# Main-v3_0.net
KiCad netlist of a schematic drawn in EAGLE
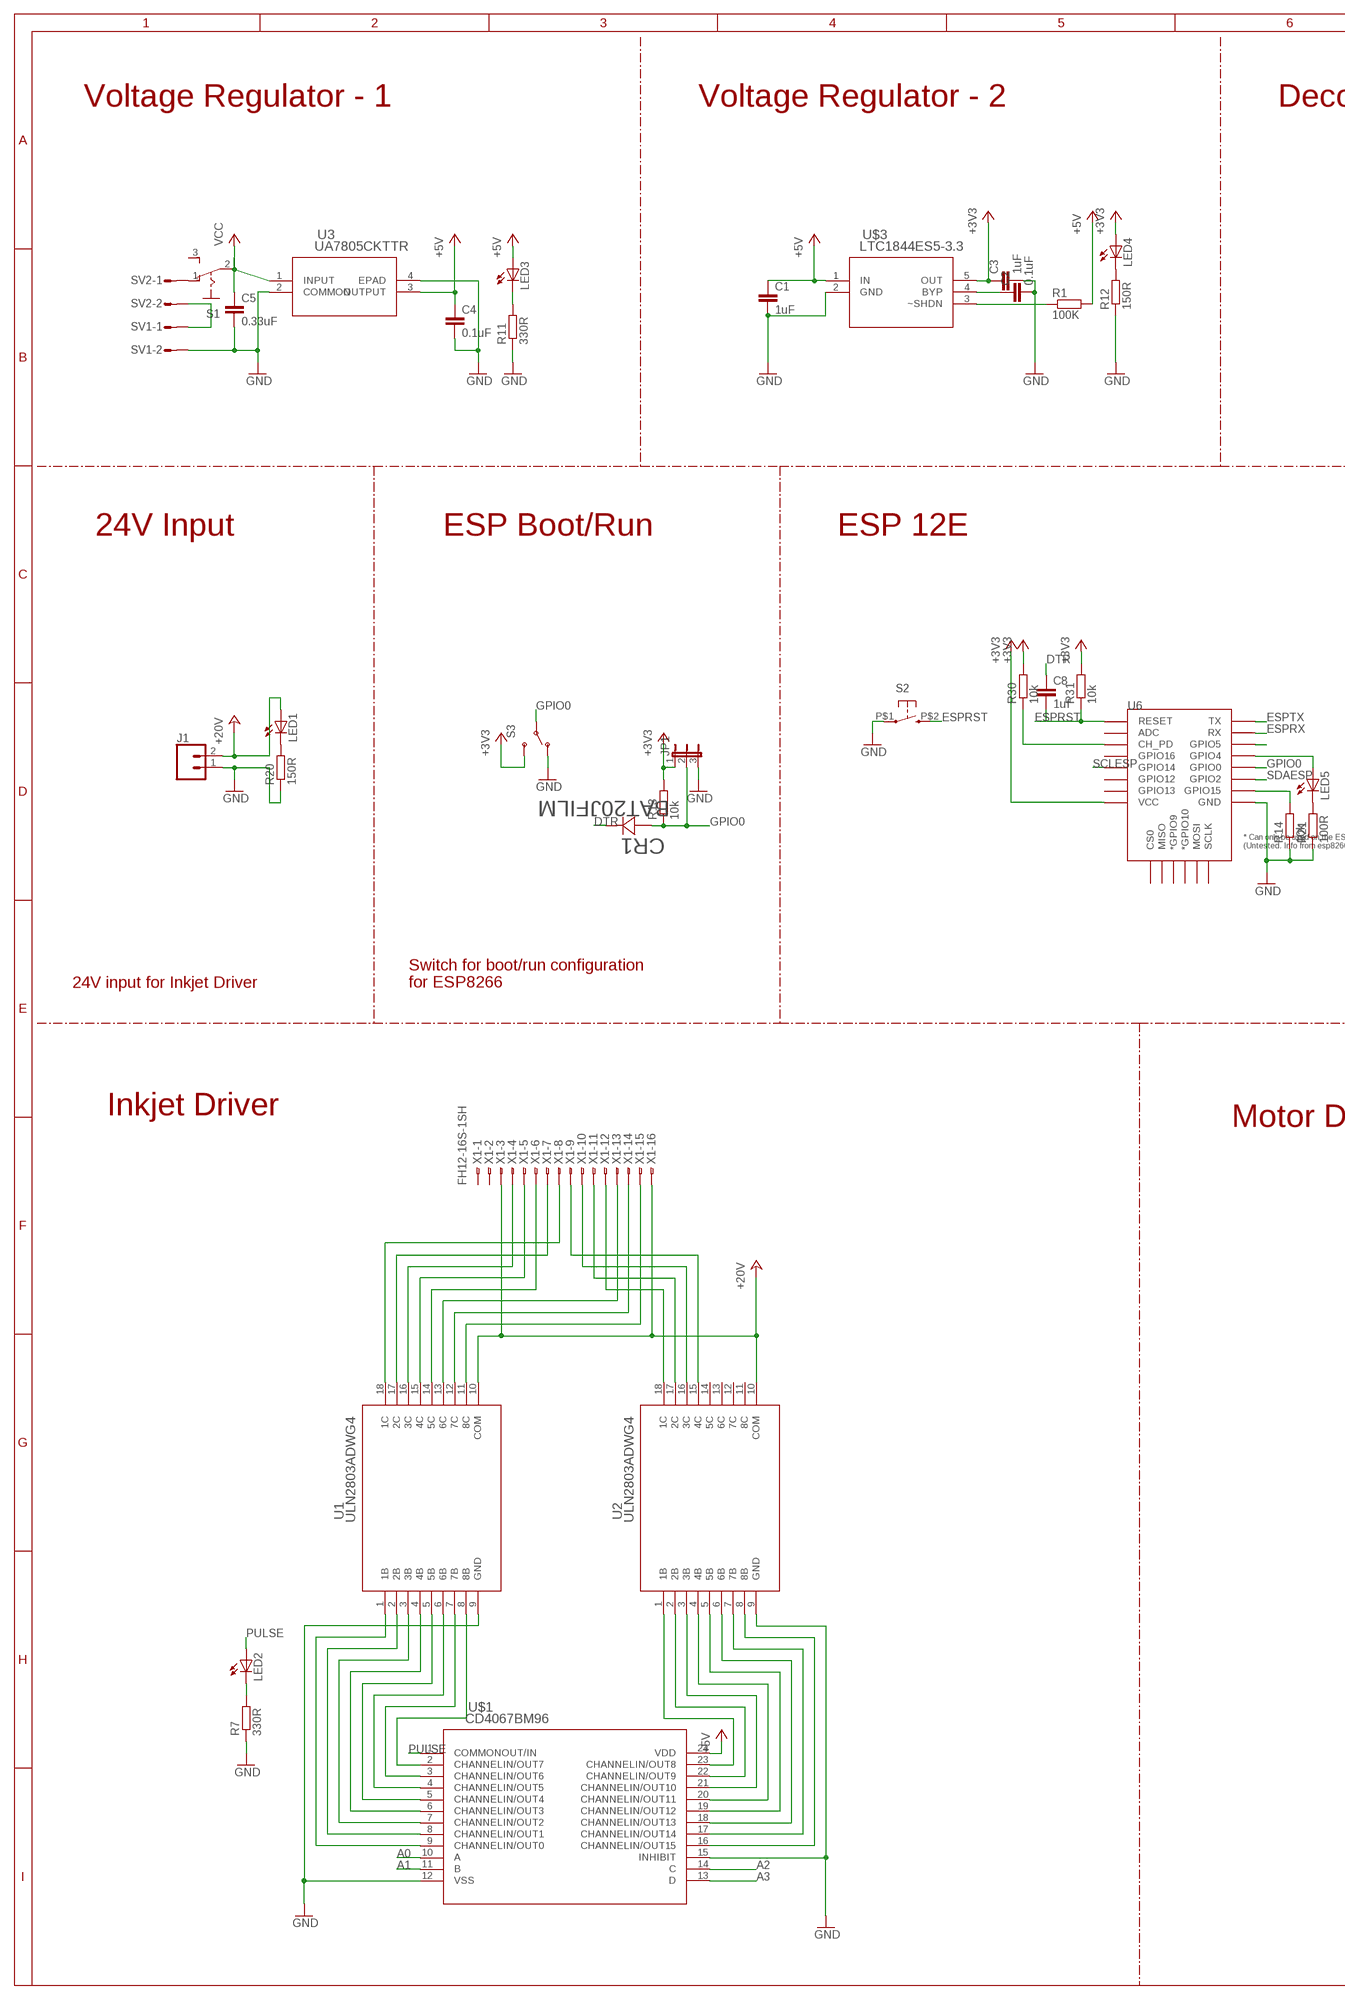
[diagram p0: schematic, sheet 1, part 1 of 2]
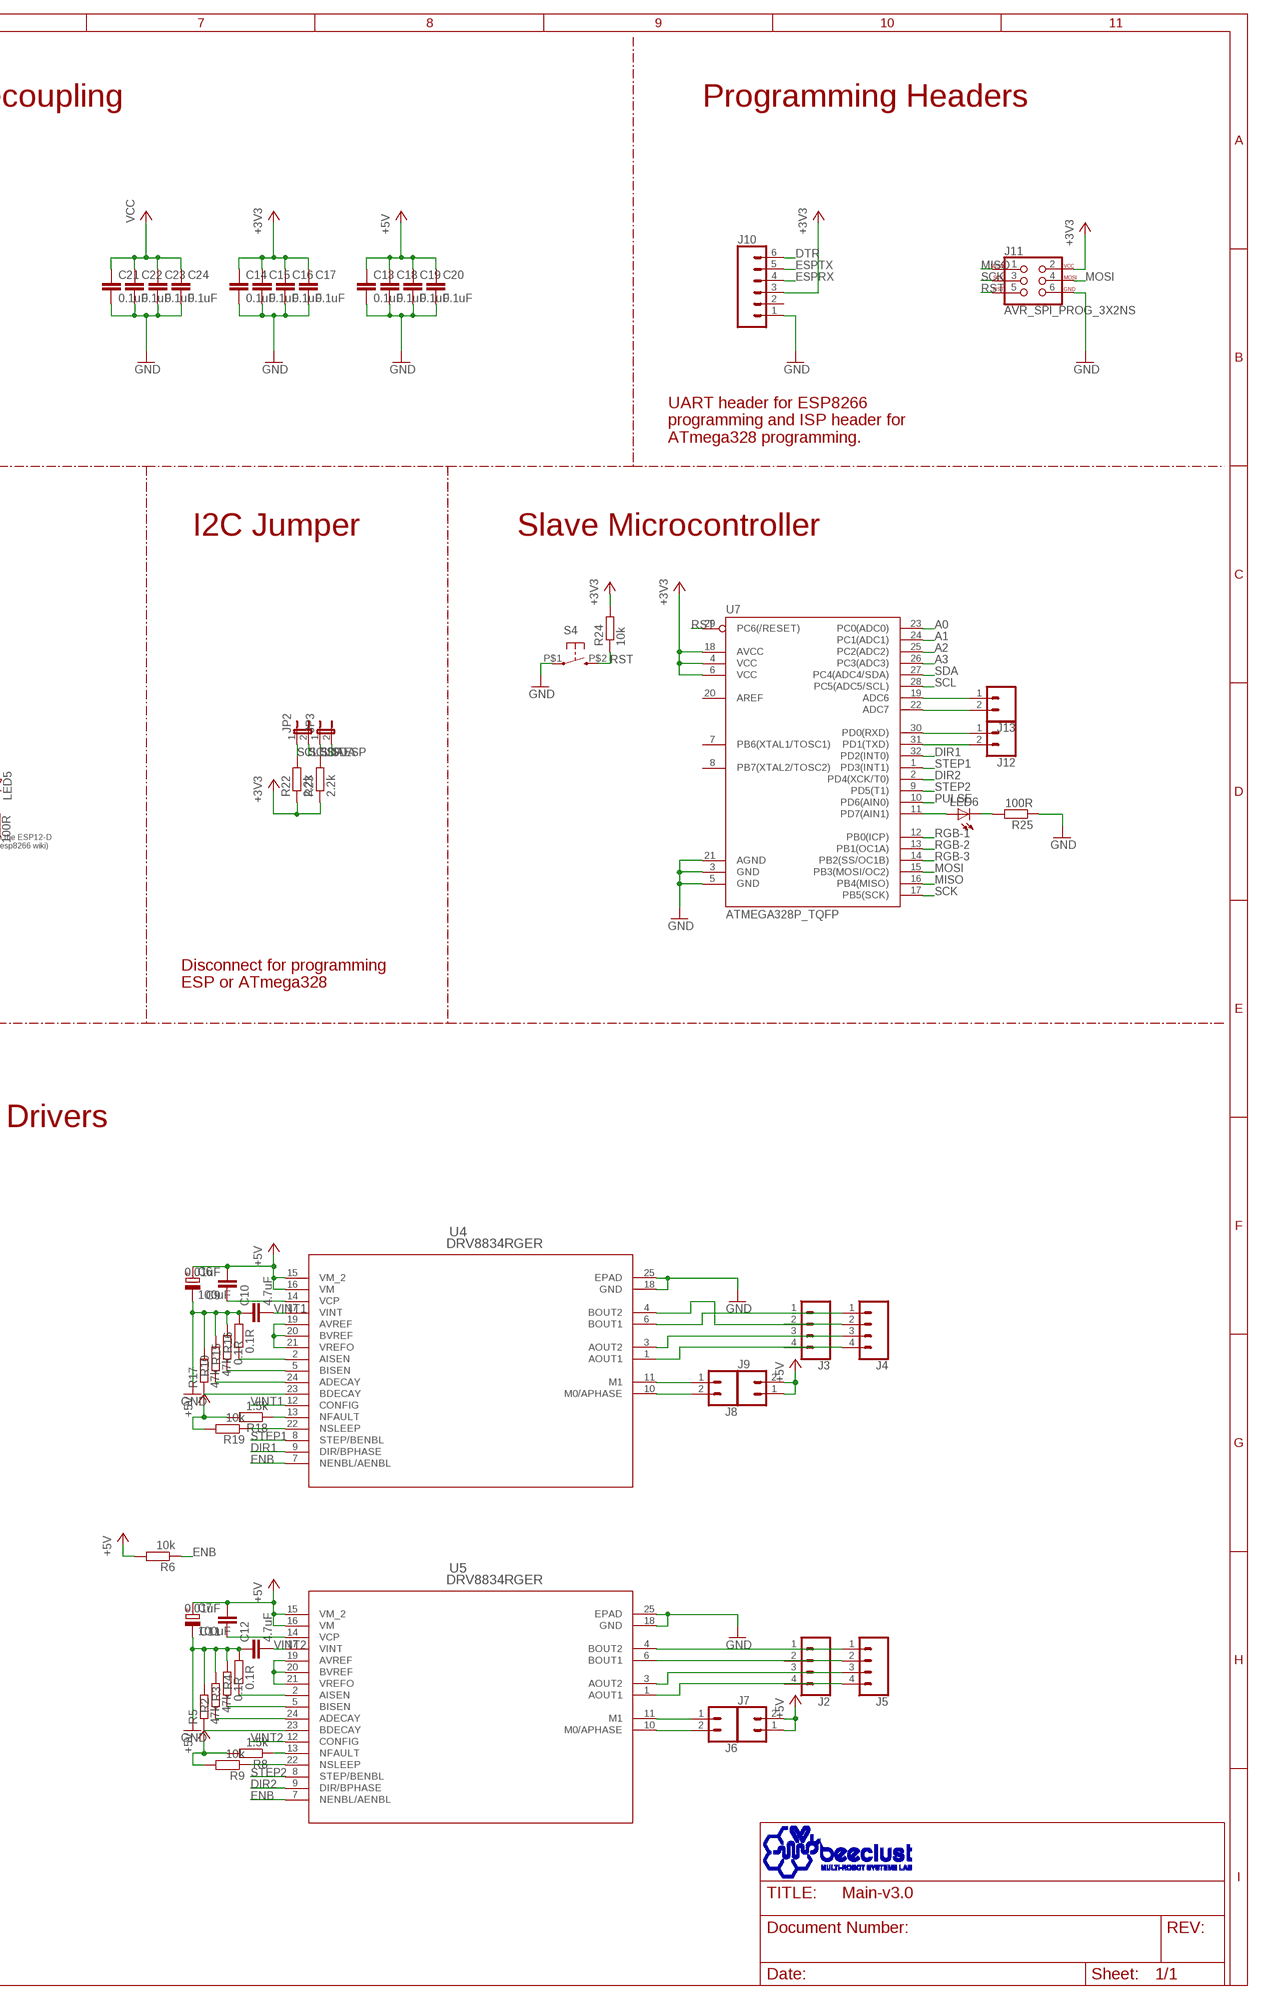
[diagram p1: schematic, sheet 1, part 2 of 2]

(export (version "E")
  (design (tool "Eeschema 10.0.6"))
  (components
    (comp (ref "C1")
      (value "1uF")
      (footprint "eagle-import:C0603")
      (libsource (lib "eagle-import") (part "C-EUC0603"))
    )
    (comp (ref "C2")
      (value "0.1uF")
      (footprint "eagle-import:C0603")
      (libsource (lib "eagle-import") (part "C-EUC0603"))
    )
    (comp (ref "C3")
      (value "1uF")
      (footprint "eagle-import:C0603")
      (libsource (lib "eagle-import") (part "C-EUC0603"))
    )
    (comp (ref "C4")
      (value "0.1uF")
      (footprint "eagle-import:C0603")
      (libsource (lib "eagle-import") (part "C-EUC0603"))
    )
    (comp (ref "C5")
      (value "0.33uF")
      (footprint "eagle-import:C0603")
      (libsource (lib "eagle-import") (part "C-EUC0603"))
    )
    (comp (ref "C6")
      (value "100uF")
      (footprint "eagle-import:E5-5")
      (libsource (lib "eagle-import") (part "CPOL-EUE5-5"))
    )
    (comp (ref "C7")
      (value "100uF")
      (footprint "eagle-import:E5-5")
      (libsource (lib "eagle-import") (part "CPOL-EUE5-5"))
    )
    (comp (ref "C8")
      (value "1uf")
      (footprint "eagle-import:C0603")
      (libsource (lib "eagle-import") (part "resistor_348_C-EUC0603"))
    )
    (comp (ref "C9")
      (value "0.01uF")
      (footprint "eagle-import:C0603K")
      (libsource (lib "eagle-import") (part "resistor_348_C-EUC0603K"))
    )
    (comp (ref "C10")
      (value "4.7uF")
      (footprint "eagle-import:C0603K")
      (libsource (lib "eagle-import") (part "resistor_348_C-EUC0603K"))
    )
    (comp (ref "C11")
      (value "0.01uF")
      (footprint "eagle-import:C0603K")
      (libsource (lib "eagle-import") (part "resistor_348_C-EUC0603K"))
    )
    (comp (ref "C12")
      (value "4.7uF")
      (footprint "eagle-import:C0603K")
      (libsource (lib "eagle-import") (part "resistor_348_C-EUC0603K"))
    )
    (comp (ref "C13")
      (value "0.1uF")
      (footprint "eagle-import:C0603")
      (libsource (lib "eagle-import") (part "C-EUC0603"))
    )
    (comp (ref "C14")
      (value "0.1uF")
      (footprint "eagle-import:C0603")
      (libsource (lib "eagle-import") (part "C-EUC0603"))
    )
    (comp (ref "C15")
      (value "0.1uF")
      (footprint "eagle-import:C0603")
      (libsource (lib "eagle-import") (part "C-EUC0603"))
    )
    (comp (ref "C16")
      (value "0.1uF")
      (footprint "eagle-import:C0603")
      (libsource (lib "eagle-import") (part "C-EUC0603"))
    )
    (comp (ref "C17")
      (value "0.1uF")
      (footprint "eagle-import:C0603")
      (libsource (lib "eagle-import") (part "C-EUC0603"))
    )
    (comp (ref "C18")
      (value "0.1uF")
      (footprint "eagle-import:C0603")
      (libsource (lib "eagle-import") (part "C-EUC0603"))
    )
    (comp (ref "C19")
      (value "0.1uF")
      (footprint "eagle-import:C0603")
      (libsource (lib "eagle-import") (part "C-EUC0603"))
    )
    (comp (ref "C20")
      (value "0.1uF")
      (footprint "eagle-import:C0603")
      (libsource (lib "eagle-import") (part "C-EUC0603"))
    )
    (comp (ref "C21")
      (value "0.1uF")
      (footprint "eagle-import:C0603")
      (libsource (lib "eagle-import") (part "C-EUC0603"))
    )
    (comp (ref "C22")
      (value "0.1uF")
      (footprint "eagle-import:C0603")
      (libsource (lib "eagle-import") (part "C-EUC0603"))
    )
    (comp (ref "C23")
      (value "0.1uF")
      (footprint "eagle-import:C0603")
      (libsource (lib "eagle-import") (part "C-EUC0603"))
    )
    (comp (ref "C24")
      (value "0.1uF")
      (footprint "eagle-import:C0603")
      (libsource (lib "eagle-import") (part "C-EUC0603"))
    )
    (comp (ref "CR1")
      (value "BAT20JFILM")
      (footprint "eagle-import:SOD-323")
      (libsource (lib "eagle-import") (part "BAT20JFILM"))
    )
    (comp (ref "J1")
      (value "CONN_02")
      (footprint "eagle-import:1X02")
      (libsource (lib "eagle-import") (part "CONN_02"))
    )
    (comp (ref "J2")
      (value "CONN_04")
      (footprint "eagle-import:1X04")
      (libsource (lib "eagle-import") (part "CONN_04"))
    )
    (comp (ref "J3")
      (value "CONN_04")
      (footprint "eagle-import:1X04")
      (libsource (lib "eagle-import") (part "CONN_04"))
    )
    (comp (ref "J4")
      (value "CONN_04")
      (footprint "eagle-import:1X04")
      (libsource (lib "eagle-import") (part "CONN_04"))
    )
    (comp (ref "J5")
      (value "CONN_04")
      (footprint "eagle-import:1X04")
      (libsource (lib "eagle-import") (part "CONN_04"))
    )
    (comp (ref "J6")
      (value "CONN_02")
      (footprint "eagle-import:1X02")
      (libsource (lib "eagle-import") (part "CONN_02"))
    )
    (comp (ref "J7")
      (value "CONN_02")
      (footprint "eagle-import:1X02")
      (libsource (lib "eagle-import") (part "CONN_02"))
    )
    (comp (ref "J8")
      (value "CONN_02")
      (footprint "eagle-import:1X02")
      (libsource (lib "eagle-import") (part "CONN_02"))
    )
    (comp (ref "J9")
      (value "CONN_02")
      (footprint "eagle-import:1X02")
      (libsource (lib "eagle-import") (part "CONN_02"))
    )
    (comp (ref "J10")
      (value "CONN_06NO_SILK_NO_POP")
      (footprint "eagle-import:1X06_NO_SILK")
      (libsource (lib "eagle-import") (part "CONN_06NO_SILK_NO_POP"))
    )
    (comp (ref "J11")
      (value "AVR_SPI_PROG_3X2NS")
      (footprint "eagle-import:2X3-NS")
      (libsource (lib "eagle-import") (part "AVR_SPI_PROG_3X2NS"))
    )
    (comp (ref "J12")
      (value "CONN_02")
      (footprint "eagle-import:1X02")
      (libsource (lib "eagle-import") (part "CONN_02"))
    )
    (comp (ref "J13")
      (value "CONN_02")
      (footprint "eagle-import:1X02")
      (libsource (lib "eagle-import") (part "CONN_02"))
    )
    (comp (ref "JP1")
      (value "JP2E")
      (footprint "eagle-import:JP2")
      (libsource (lib "eagle-import") (part "JP2E"))
    )
    (comp (ref "JP2")
      (value "JP1E")
      (footprint "eagle-import:JP1")
      (libsource (lib "eagle-import") (part "JP1E"))
    )
    (comp (ref "JP3")
      (value "JP1E")
      (footprint "eagle-import:JP1")
      (libsource (lib "eagle-import") (part "JP1E"))
    )
    (comp (ref "LED1")
      (value "LEDSML0603")
      (footprint "eagle-import:SML0603")
      (libsource (lib "eagle-import") (part "LEDSML0603"))
    )
    (comp (ref "LED2")
      (value "LEDSML0603")
      (footprint "eagle-import:SML0603")
      (libsource (lib "eagle-import") (part "LEDSML0603"))
    )
    (comp (ref "LED3")
      (value "LEDSML0603")
      (footprint "eagle-import:SML0603")
      (libsource (lib "eagle-import") (part "LEDSML0603"))
    )
    (comp (ref "LED4")
      (value "LEDSML0603")
      (footprint "eagle-import:SML0603")
      (libsource (lib "eagle-import") (part "LEDSML0603"))
    )
    (comp (ref "LED5")
      (value "LEDSML0603")
      (footprint "eagle-import:SML0603")
      (libsource (lib "eagle-import") (part "LEDSML0603"))
    )
    (comp (ref "LED6")
      (value "LEDSML0603")
      (footprint "eagle-import:SML0603")
      (libsource (lib "eagle-import") (part "LEDSML0603"))
    )
    (comp (ref "R1")
      (value "100K")
      (footprint "eagle-import:R0603")
      (libsource (lib "eagle-import") (part "R-EU_R0603"))
    )
    (comp (ref "R2")
      (value "47k")
      (footprint "eagle-import:R0402")
      (libsource (lib "eagle-import") (part "resistor_348_R-EU_R0402"))
    )
    (comp (ref "R3")
      (value "0.1R")
      (footprint "eagle-import:R0402")
      (libsource (lib "eagle-import") (part "resistor_348_R-EU_R0402"))
    )
    (comp (ref "R4")
      (value "0.1R")
      (footprint "eagle-import:R0402")
      (libsource (lib "eagle-import") (part "resistor_348_R-EU_R0402"))
    )
    (comp (ref "R5")
      (value "47k")
      (footprint "eagle-import:R0402")
      (libsource (lib "eagle-import") (part "resistor_348_R-EU_R0402"))
    )
    (comp (ref "R6")
      (value "10k")
      (footprint "eagle-import:R0402")
      (libsource (lib "eagle-import") (part "resistor_348_R-EU_R0402"))
    )
    (comp (ref "R7")
      (value "330R")
      (footprint "eagle-import:R0603")
      (libsource (lib "eagle-import") (part "R-EU_R0603"))
    )
    (comp (ref "R8")
      (value "1.5k")
      (footprint "eagle-import:R0402")
      (libsource (lib "eagle-import") (part "resistor_348_R-EU_R0402"))
    )
    (comp (ref "R9")
      (value "10k")
      (footprint "eagle-import:R0402")
      (libsource (lib "eagle-import") (part "resistor_348_R-EU_R0402"))
    )
    (comp (ref "R10")
      (value "47k")
      (footprint "eagle-import:R0402")
      (libsource (lib "eagle-import") (part "resistor_348_R-EU_R0402"))
    )
    (comp (ref "R11")
      (value "330R")
      (footprint "eagle-import:R0603")
      (libsource (lib "eagle-import") (part "R-EU_R0603"))
    )
    (comp (ref "R12")
      (value "150R")
      (footprint "eagle-import:R0603")
      (libsource (lib "eagle-import") (part "R-EU_R0603"))
    )
    (comp (ref "R13")
      (value "10k")
      (footprint "eagle-import:R0603")
      (libsource (lib "eagle-import") (part "R-EU_R0603"))
    )
    (comp (ref "R14")
      (value "10k")
      (footprint "eagle-import:R0603")
      (libsource (lib "eagle-import") (part "R-EU_R0603"))
    )
    (comp (ref "R15")
      (value "0.1R")
      (footprint "eagle-import:R0402")
      (libsource (lib "eagle-import") (part "resistor_348_R-EU_R0402"))
    )
    (comp (ref "R16")
      (value "0.1R")
      (footprint "eagle-import:R0402")
      (libsource (lib "eagle-import") (part "resistor_348_R-EU_R0402"))
    )
    (comp (ref "R17")
      (value "47k")
      (footprint "eagle-import:R0402")
      (libsource (lib "eagle-import") (part "resistor_348_R-EU_R0402"))
    )
    (comp (ref "R18")
      (value "1.5k")
      (footprint "eagle-import:R0402")
      (libsource (lib "eagle-import") (part "resistor_348_R-EU_R0402"))
    )
    (comp (ref "R19")
      (value "10k")
      (footprint "eagle-import:R0402")
      (libsource (lib "eagle-import") (part "resistor_348_R-EU_R0402"))
    )
    (comp (ref "R20")
      (value "150R")
      (footprint "eagle-import:R0603")
      (libsource (lib "eagle-import") (part "R-EU_R0603"))
    )
    (comp (ref "R21")
      (value "100R")
      (footprint "eagle-import:R0603")
      (libsource (lib "eagle-import") (part "R-EU_R0603"))
    )
    (comp (ref "R22")
      (value "2.2k")
      (footprint "eagle-import:R0603")
      (libsource (lib "eagle-import") (part "R-EU_R0603"))
    )
    (comp (ref "R23")
      (value "2.2k")
      (footprint "eagle-import:R0603")
      (libsource (lib "eagle-import") (part "R-EU_R0603"))
    )
    (comp (ref "R24")
      (value "10k")
      (footprint "eagle-import:R0603")
      (libsource (lib "eagle-import") (part "R-EU_R0603"))
    )
    (comp (ref "R25")
      (value "100R")
      (footprint "eagle-import:R0603")
      (libsource (lib "eagle-import") (part "R-EU_R0603"))
    )
    (comp (ref "R30")
      (value "10k")
      (footprint "eagle-import:R0603")
      (libsource (lib "eagle-import") (part "R-EU_R0603"))
    )
    (comp (ref "R31")
      (value "10k")
      (footprint "eagle-import:R0603")
      (libsource (lib "eagle-import") (part "R-EU_R0603"))
    )
    (comp (ref "S1")
      (value "255SB")
      (footprint "eagle-import:255SB")
      (libsource (lib "eagle-import") (part "255SB"))
    )
    (comp (ref "S2")
      (value "KSS")
      (footprint "eagle-import:KSS")
      (libsource (lib "eagle-import") (part "KSS"))
    )
    (comp (ref "S3")
      (value "SWITCH-SPDT-SMD-A")
      (footprint "eagle-import:SWITCH-SPST-SMD-A")
      (libsource (lib "eagle-import") (part "SWITCH-SPDT-SMD-A"))
    )
    (comp (ref "S4")
      (value "KSS")
      (footprint "eagle-import:KSS")
      (libsource (lib "eagle-import") (part "KSS"))
    )
    (comp (ref "SV1")
      (value "L02P")
      (footprint "eagle-import:L02P")
      (libsource (lib "eagle-import") (part "L02P"))
    )
    (comp (ref "SV2")
      (value "L02P")
      (footprint "eagle-import:L02P")
      (libsource (lib "eagle-import") (part "L02P"))
    )
    (comp (ref "U$1")
      (value "CD4067BM96")
      (footprint "eagle-import:DW24")
      (fields (field (name "MANUFACTURER_PART_NUMBER") "CD4067B_DW_24"))
      (libsource (lib "eagle-import") (part "CD4067BM96"))
    )
    (comp (ref "U$2")
      (value "BEECLUST-LOGO")
      (footprint "eagle-import:LOGO")
      (libsource (lib "eagle-import") (part "BEECLUST-LOGO"))
    )
    (comp (ref "U$3")
      (value "LTC1844ES5-3.3")
      (footprint "eagle-import:TSOT-23_S5")
      (libsource (lib "eagle-import") (part "LTC1844ES5-3.3"))
    )
    (comp (ref "U1")
      (value "ULN2803ADWG4")
      (footprint "eagle-import:DW18")
      (libsource (lib "eagle-import") (part "ULN2803ADWG4"))
    )
    (comp (ref "U2")
      (value "ULN2803ADWG4")
      (footprint "eagle-import:DW18")
      (libsource (lib "eagle-import") (part "ULN2803ADWG4"))
    )
    (comp (ref "U3")
      (value "UA7805CKTTR")
      (footprint "eagle-import:KTT3_6P22X6P6")
      (libsource (lib "eagle-import") (part "UA7805CKTTR"))
    )
    (comp (ref "U4")
      (value "DRV8834RGER")
      (footprint "eagle-import:RGE24_2P45X2P45")
      (libsource (lib "eagle-import") (part "DRV8834RGER"))
    )
    (comp (ref "U5")
      (value "DRV8834RGER")
      (footprint "eagle-import:RGE24_2P45X2P45")
      (libsource (lib "eagle-import") (part "DRV8834RGER"))
    )
    (comp (ref "U6")
      (value "ESP12ESMD")
      (footprint "eagle-import:ESP12E-SMD")
      (libsource (lib "eagle-import") (part "ESP12ESMD"))
    )
    (comp (ref "U7")
      (value "ATMEGA328P_TQFP")
      (footprint "eagle-import:TQFP32-08")
      (libsource (lib "eagle-import") (part "ATMEGA328P_TQFP"))
    )
    (comp (ref "X1")
      (value "FH12-16S-1SH")
      (footprint "eagle-import:FH12-16S-1SH")
      (libsource (lib "eagle-import") (part "FH12-16S-1SH"))
    )
  )
  (nets
    (net (code "1") (name "+3V3") (class "Default")
      (node (ref "C14") (pin "1") (pinfunction "1_1") (pintype "passive"))
      (node (ref "C15") (pin "1") (pinfunction "1_1") (pintype "passive"))
      (node (ref "C16") (pin "1") (pinfunction "1_1") (pintype "passive"))
      (node (ref "C17") (pin "1") (pinfunction "1_1") (pintype "passive"))
      (node (ref "C3") (pin "1") (pinfunction "1_1") (pintype "passive"))
      (node (ref "J10") (pin "3") (pinfunction "3_3") (pintype "passive"))
      (node (ref "J11") (pin "2") (pinfunction "2_2") (pintype "passive"))
      (node (ref "JP1") (pin "1") (pinfunction "1_1") (pintype "passive"))
      (node (ref "LED4") (pin "A") (pinfunction "A_A") (pintype "passive"))
      (node (ref "R13") (pin "2") (pinfunction "2_2") (pintype "passive"))
      (node (ref "R22") (pin "1") (pinfunction "1_1") (pintype "passive"))
      (node (ref "R23") (pin "1") (pinfunction "1_1") (pintype "passive"))
      (node (ref "R24") (pin "2") (pinfunction "2_2") (pintype "passive"))
      (node (ref "R30") (pin "2") (pinfunction "2_2") (pintype "passive"))
      (node (ref "R31") (pin "2") (pinfunction "2_2") (pintype "passive"))
      (node (ref "S3") (pin "3") (pinfunction "S_3") (pintype "passive"))
      (node (ref "U$3") (pin "5") (pinfunction "OUT_5") (pintype "passive"))
      (node (ref "U6") (pin "VCC") (pinfunction "VCC_VCC") (pintype "bidirectional"))
      (node (ref "U7") (pin "18") (pinfunction "AVCC_18") (pintype "bidirectional"))
      (node (ref "U7") (pin "4") (pinfunction "VCC_4") (pintype "bidirectional"))
      (node (ref "U7") (pin "6") (pinfunction "VCC_6") (pintype "bidirectional"))
    )
    (net (code "2") (name "+5V") (class "Default")
      (node (ref "C1") (pin "1") (pinfunction "1_1") (pintype "passive"))
      (node (ref "C11") (pin "2") (pinfunction "2_2") (pintype "passive"))
      (node (ref "C13") (pin "1") (pinfunction "1_1") (pintype "passive"))
      (node (ref "C18") (pin "1") (pinfunction "1_1") (pintype "passive"))
      (node (ref "C19") (pin "1") (pinfunction "1_1") (pintype "passive"))
      (node (ref "C20") (pin "1") (pinfunction "1_1") (pintype "passive"))
      (node (ref "C4") (pin "1") (pinfunction "1_1") (pintype "passive"))
      (node (ref "C6") (pin "+") (pinfunction "+_+") (pintype "passive"))
      (node (ref "C7") (pin "+") (pinfunction "+_+") (pintype "passive"))
      (node (ref "C9") (pin "2") (pinfunction "2_2") (pintype "passive"))
      (node (ref "J7") (pin "1") (pinfunction "1_1") (pintype "passive"))
      (node (ref "J7") (pin "2") (pinfunction "2_2") (pintype "passive"))
      (node (ref "J9") (pin "1") (pinfunction "1_1") (pintype "passive"))
      (node (ref "J9") (pin "2") (pinfunction "2_2") (pintype "passive"))
      (node (ref "LED3") (pin "A") (pinfunction "A_A") (pintype "passive"))
      (node (ref "R1") (pin "2") (pinfunction "2_2") (pintype "passive"))
      (node (ref "R18") (pin "2") (pinfunction "2_2") (pintype "passive"))
      (node (ref "R19") (pin "2") (pinfunction "2_2") (pintype "passive"))
      (node (ref "R6") (pin "2") (pinfunction "2_2") (pintype "passive"))
      (node (ref "R8") (pin "2") (pinfunction "2_2") (pintype "passive"))
      (node (ref "R9") (pin "2") (pinfunction "2_2") (pintype "passive"))
      (node (ref "U$1") (pin "24") (pinfunction "VDD_24") (pintype "power_in"))
      (node (ref "U$3") (pin "1") (pinfunction "IN_1") (pintype "passive"))
      (node (ref "U3") (pin "3") (pinfunction "OUTPUT_3") (pintype "output"))
      (node (ref "U4") (pin "15") (pinfunction "VM_2_15") (pintype "power_in"))
      (node (ref "U4") (pin "16") (pinfunction "VM_16") (pintype "power_in"))
      (node (ref "U5") (pin "15") (pinfunction "VM_2_15") (pintype "power_in"))
      (node (ref "U5") (pin "16") (pinfunction "VM_16") (pintype "power_in"))
    )
    (net (code "3") (name "+20V") (class "Default")
      (node (ref "J1") (pin "2") (pinfunction "2_2") (pintype "passive"))
      (node (ref "LED1") (pin "A") (pinfunction "A_A") (pintype "passive"))
      (node (ref "U1") (pin "10") (pinfunction "COM_10") (pintype "passive"))
      (node (ref "U2") (pin "10") (pinfunction "COM_10") (pintype "passive"))
      (node (ref "X1") (pin "16") (pinfunction "1_16") (pintype "passive"))
      (node (ref "X1") (pin "3") (pinfunction "1_3") (pintype "passive"))
    )
    (net (code "4") (name "/A0") (class "Default")
      (node (ref "U$1") (pin "10") (pinfunction "A_10") (pintype "passive"))
      (node (ref "U7") (pin "23") (pinfunction "PC0(ADC0)_23") (pintype "bidirectional"))
    )
    (net (code "5") (name "/A1") (class "Default")
      (node (ref "U$1") (pin "11") (pinfunction "B_11") (pintype "passive"))
      (node (ref "U7") (pin "24") (pinfunction "PC1(ADC1)_24") (pintype "bidirectional"))
    )
    (net (code "6") (name "/A2") (class "Default")
      (node (ref "U$1") (pin "14") (pinfunction "C_14") (pintype "passive"))
      (node (ref "U7") (pin "25") (pinfunction "PC2(ADC2)_25") (pintype "bidirectional"))
    )
    (net (code "7") (name "/A3") (class "Default")
      (node (ref "U$1") (pin "13") (pinfunction "D_13") (pintype "passive"))
      (node (ref "U7") (pin "26") (pinfunction "PC3(ADC3)_26") (pintype "bidirectional"))
    )
    (net (code "8") (name "/DIR1") (class "Default")
      (node (ref "U4") (pin "9") (pinfunction "DIR/BPHASE_9") (pintype "input"))
      (node (ref "U7") (pin "32") (pinfunction "PD2(INT0)_32") (pintype "bidirectional"))
    )
    (net (code "9") (name "/DIR2") (class "Default")
      (node (ref "U5") (pin "9") (pinfunction "DIR/BPHASE_9") (pintype "input"))
      (node (ref "U7") (pin "2") (pinfunction "PD4(XCK/T0)_2") (pintype "bidirectional"))
    )
    (net (code "10") (name "/DTR") (class "Default")
      (node (ref "C8") (pin "1") (pinfunction "1_1") (pintype "passive"))
      (node (ref "CR1") (pin "1") (pinfunction "11_1") (pintype "passive"))
      (node (ref "J10") (pin "6") (pinfunction "6_6") (pintype "passive"))
    )
    (net (code "11") (name "/ENB") (class "Default")
      (node (ref "R6") (pin "1") (pinfunction "1_1") (pintype "passive"))
      (node (ref "U4") (pin "7") (pinfunction "NENBL/AENBL_7") (pintype "input"))
      (node (ref "U5") (pin "7") (pinfunction "NENBL/AENBL_7") (pintype "input"))
    )
    (net (code "12") (name "/ESPRST") (class "Default")
      (node (ref "C8") (pin "2") (pinfunction "2_2") (pintype "passive"))
      (node (ref "R31") (pin "1") (pinfunction "1_1") (pintype "passive"))
      (node (ref "S2") (pin "P$2") (pinfunction "3_P$2") (pintype "passive"))
      (node (ref "U6") (pin "RESET") (pinfunction "RESET_RESET") (pintype "bidirectional"))
    )
    (net (code "13") (name "/ESPRX") (class "Default")
      (node (ref "J10") (pin "4") (pinfunction "4_4") (pintype "passive"))
      (node (ref "U6") (pin "RXD0") (pinfunction "RX_RXD0") (pintype "bidirectional"))
    )
    (net (code "14") (name "/ESPTX") (class "Default")
      (node (ref "J10") (pin "5") (pinfunction "5_5") (pintype "passive"))
      (node (ref "U6") (pin "TXD0") (pinfunction "TX_TXD0") (pintype "bidirectional"))
    )
    (net (code "15") (name "/GPIO0") (class "Default")
      (node (ref "CR1") (pin "2") (pinfunction "22_2") (pintype "passive"))
      (node (ref "JP1") (pin "2") (pinfunction "2_2") (pintype "passive"))
      (node (ref "R13") (pin "1") (pinfunction "1_1") (pintype "passive"))
      (node (ref "S3") (pin "2") (pinfunction "P_2") (pintype "passive"))
      (node (ref "U6") (pin "GPIO0") (pinfunction "GPIO0_GPIO0") (pintype "bidirectional"))
    )
    (net (code "16") (name "/MISO") (class "Default")
      (node (ref "J11") (pin "1") (pinfunction "1_1") (pintype "passive"))
      (node (ref "U7") (pin "16") (pinfunction "PB4(MISO)_16") (pintype "bidirectional"))
    )
    (net (code "17") (name "/MOSI") (class "Default")
      (node (ref "J11") (pin "4") (pinfunction "4_4") (pintype "passive"))
      (node (ref "U7") (pin "15") (pinfunction "PB3(MOSI/OC2)_15") (pintype "bidirectional"))
    )
    (net (code "18") (name "/PULSE") (class "Default")
      (node (ref "LED2") (pin "A") (pinfunction "A_A") (pintype "passive"))
      (node (ref "U$1") (pin "1") (pinfunction "COMMONOUT/IN_1") (pintype "bidirectional"))
      (node (ref "U7") (pin "10") (pinfunction "PD6(AIN0)_10") (pintype "bidirectional"))
    )
    (net (code "19") (name "/RGB-1") (class "Default")
      (node (ref "U7") (pin "12") (pinfunction "PB0(ICP)_12") (pintype "bidirectional"))
    )
    (net (code "20") (name "/RGB-2") (class "Default")
      (node (ref "U7") (pin "13") (pinfunction "PB1(OC1A)_13") (pintype "bidirectional"))
    )
    (net (code "21") (name "/RGB-3") (class "Default")
      (node (ref "U7") (pin "14") (pinfunction "PB2(SS/OC1B)_14") (pintype "bidirectional"))
    )
    (net (code "22") (name "/RST") (class "Default")
      (node (ref "J11") (pin "5") (pinfunction "5_5") (pintype "passive"))
      (node (ref "R24") (pin "1") (pinfunction "1_1") (pintype "passive"))
      (node (ref "S4") (pin "P$2") (pinfunction "3_P$2") (pintype "passive"))
      (node (ref "U7") (pin "29") (pinfunction "PC6(/RESET)_29") (pintype "bidirectional"))
    )
    (net (code "23") (name "/SCK") (class "Default")
      (node (ref "J11") (pin "3") (pinfunction "3_3") (pintype "passive"))
      (node (ref "U7") (pin "17") (pinfunction "PB5(SCK)_17") (pintype "bidirectional"))
    )
    (net (code "24") (name "/SCL") (class "Default")
      (node (ref "JP2") (pin "2") (pinfunction "2_2") (pintype "passive"))
      (node (ref "U7") (pin "28") (pinfunction "PC5(ADC5/SCL)_28") (pintype "bidirectional"))
    )
    (net (code "25") (name "/SCLESP") (class "Default")
      (node (ref "JP2") (pin "1") (pinfunction "1_1") (pintype "passive"))
      (node (ref "R22") (pin "2") (pinfunction "2_2") (pintype "passive"))
      (node (ref "U6") (pin "GPIO14") (pinfunction "GPIO14_GPIO14") (pintype "bidirectional"))
    )
    (net (code "26") (name "/SDA") (class "Default")
      (node (ref "JP3") (pin "2") (pinfunction "2_2") (pintype "passive"))
      (node (ref "U7") (pin "27") (pinfunction "PC4(ADC4/SDA)_27") (pintype "bidirectional"))
    )
    (net (code "27") (name "/SDAESP") (class "Default")
      (node (ref "JP3") (pin "1") (pinfunction "1_1") (pintype "passive"))
      (node (ref "R23") (pin "2") (pinfunction "2_2") (pintype "passive"))
      (node (ref "U6") (pin "GPIO2") (pinfunction "GPIO2_GPIO2") (pintype "bidirectional"))
    )
    (net (code "28") (name "/STEP1") (class "Default")
      (node (ref "U4") (pin "8") (pinfunction "STEP/BENBL_8") (pintype "input"))
      (node (ref "U7") (pin "1") (pinfunction "PD3(INT1)_1") (pintype "bidirectional"))
    )
    (net (code "29") (name "/STEP2") (class "Default")
      (node (ref "U5") (pin "8") (pinfunction "STEP/BENBL_8") (pintype "input"))
      (node (ref "U7") (pin "9") (pinfunction "PD5(T1)_9") (pintype "bidirectional"))
    )
    (net (code "30") (name "/VINT1") (class "Default")
      (node (ref "C10") (pin "2") (pinfunction "2_2") (pintype "passive"))
      (node (ref "U4") (pin "12") (pinfunction "CONFIG_12") (pintype "input"))
      (node (ref "U4") (pin "17") (pinfunction "VINT_17") (pintype "passive"))
    )
    (net (code "31") (name "/VINT2") (class "Default")
      (node (ref "C12") (pin "2") (pinfunction "2_2") (pintype "passive"))
      (node (ref "U5") (pin "12") (pinfunction "CONFIG_12") (pintype "input"))
      (node (ref "U5") (pin "17") (pinfunction "VINT_17") (pintype "passive"))
    )
    (net (code "32") (name "GND") (class "Default")
      (node (ref "C1") (pin "2") (pinfunction "2_2") (pintype "passive"))
      (node (ref "C10") (pin "1") (pinfunction "1_1") (pintype "passive"))
      (node (ref "C12") (pin "1") (pinfunction "1_1") (pintype "passive"))
      (node (ref "C13") (pin "2") (pinfunction "2_2") (pintype "passive"))
      (node (ref "C14") (pin "2") (pinfunction "2_2") (pintype "passive"))
      (node (ref "C15") (pin "2") (pinfunction "2_2") (pintype "passive"))
      (node (ref "C16") (pin "2") (pinfunction "2_2") (pintype "passive"))
      (node (ref "C17") (pin "2") (pinfunction "2_2") (pintype "passive"))
      (node (ref "C18") (pin "2") (pinfunction "2_2") (pintype "passive"))
      (node (ref "C19") (pin "2") (pinfunction "2_2") (pintype "passive"))
      (node (ref "C2") (pin "2") (pinfunction "2_2") (pintype "passive"))
      (node (ref "C20") (pin "2") (pinfunction "2_2") (pintype "passive"))
      (node (ref "C21") (pin "2") (pinfunction "2_2") (pintype "passive"))
      (node (ref "C22") (pin "2") (pinfunction "2_2") (pintype "passive"))
      (node (ref "C23") (pin "2") (pinfunction "2_2") (pintype "passive"))
      (node (ref "C24") (pin "2") (pinfunction "2_2") (pintype "passive"))
      (node (ref "C3") (pin "2") (pinfunction "2_2") (pintype "passive"))
      (node (ref "C4") (pin "2") (pinfunction "2_2") (pintype "passive"))
      (node (ref "C5") (pin "2") (pinfunction "2_2") (pintype "passive"))
      (node (ref "C6") (pin "-") (pinfunction "-_-") (pintype "passive"))
      (node (ref "C7") (pin "-") (pinfunction "-_-") (pintype "passive"))
      (node (ref "J1") (pin "1") (pinfunction "1_1") (pintype "passive"))
      (node (ref "J10") (pin "1") (pinfunction "1_1") (pintype "passive"))
      (node (ref "J11") (pin "6") (pinfunction "6_6") (pintype "passive"))
      (node (ref "JP1") (pin "3") (pinfunction "3_3") (pintype "passive"))
      (node (ref "R10") (pin "2") (pinfunction "2_2") (pintype "passive"))
      (node (ref "R11") (pin "1") (pinfunction "1_1") (pintype "passive"))
      (node (ref "R12") (pin "1") (pinfunction "1_1") (pintype "passive"))
      (node (ref "R14") (pin "1") (pinfunction "1_1") (pintype "passive"))
      (node (ref "R15") (pin "2") (pinfunction "2_2") (pintype "passive"))
      (node (ref "R16") (pin "2") (pinfunction "2_2") (pintype "passive"))
      (node (ref "R17") (pin "2") (pinfunction "2_2") (pintype "passive"))
      (node (ref "R2") (pin "2") (pinfunction "2_2") (pintype "passive"))
      (node (ref "R20") (pin "1") (pinfunction "1_1") (pintype "passive"))
      (node (ref "R21") (pin "1") (pinfunction "1_1") (pintype "passive"))
      (node (ref "R25") (pin "1") (pinfunction "1_1") (pintype "passive"))
      (node (ref "R3") (pin "2") (pinfunction "2_2") (pintype "passive"))
      (node (ref "R4") (pin "2") (pinfunction "2_2") (pintype "passive"))
      (node (ref "R5") (pin "2") (pinfunction "2_2") (pintype "passive"))
      (node (ref "R7") (pin "1") (pinfunction "1_1") (pintype "passive"))
      (node (ref "S2") (pin "P$1") (pinfunction "1_P$1") (pintype "passive"))
      (node (ref "S3") (pin "1") (pinfunction "O_1") (pintype "passive"))
      (node (ref "S4") (pin "P$1") (pinfunction "1_P$1") (pintype "passive"))
      (node (ref "SV1") (pin "2") (pinfunction "S_2") (pintype "passive"))
      (node (ref "U$1") (pin "12") (pinfunction "VSS_12") (pintype "power_in"))
      (node (ref "U$1") (pin "15") (pinfunction "INHIBIT_15") (pintype "passive"))
      (node (ref "U$3") (pin "2") (pinfunction "GND_2") (pintype "passive"))
      (node (ref "U1") (pin "9") (pinfunction "GND_9") (pintype "passive"))
      (node (ref "U2") (pin "9") (pinfunction "GND_9") (pintype "passive"))
      (node (ref "U3") (pin "2") (pinfunction "COMMON_2") (pintype "power_in"))
      (node (ref "U3") (pin "4") (pinfunction "EPAD_4") (pintype "passive"))
      (node (ref "U4") (pin "18") (pinfunction "GND_18") (pintype "power_in"))
      (node (ref "U4") (pin "25") (pinfunction "EPAD_25") (pintype "passive"))
      (node (ref "U5") (pin "18") (pinfunction "GND_18") (pintype "power_in"))
      (node (ref "U5") (pin "25") (pinfunction "EPAD_25") (pintype "passive"))
      (node (ref "U6") (pin "GND") (pinfunction "GND_GND") (pintype "bidirectional"))
      (node (ref "U7") (pin "21") (pinfunction "AGND_21") (pintype "bidirectional"))
      (node (ref "U7") (pin "3") (pinfunction "GND_3") (pintype "bidirectional"))
      (node (ref "U7") (pin "5") (pinfunction "GND_5") (pintype "bidirectional"))
    )
    (net (code "33") (name "Net-(LED1-PadC)") (class "Default")
      (node (ref "LED1") (pin "C") (pinfunction "C_C") (pintype "passive"))
      (node (ref "R20") (pin "2") (pinfunction "2_2") (pintype "passive"))
    )
    (net (code "34") (name "Net-(LED2-PadC)") (class "Default")
      (node (ref "LED2") (pin "C") (pinfunction "C_C") (pintype "passive"))
      (node (ref "R7") (pin "2") (pinfunction "2_2") (pintype "passive"))
    )
    (net (code "35") (name "Net-(LED3-PadC)") (class "Default")
      (node (ref "LED3") (pin "C") (pinfunction "C_C") (pintype "passive"))
      (node (ref "R11") (pin "2") (pinfunction "2_2") (pintype "passive"))
    )
    (net (code "36") (name "Net-(LED4-PadC)") (class "Default")
      (node (ref "LED4") (pin "C") (pinfunction "C_C") (pintype "passive"))
      (node (ref "R12") (pin "2") (pinfunction "2_2") (pintype "passive"))
    )
    (net (code "37") (name "Net-(LED5-PadA)") (class "Default")
      (node (ref "LED5") (pin "A") (pinfunction "A_A") (pintype "passive"))
      (node (ref "U6") (pin "GPIO4") (pinfunction "GPIO4_GPIO4") (pintype "bidirectional"))
    )
    (net (code "38") (name "Net-(LED5-PadC)") (class "Default")
      (node (ref "LED5") (pin "C") (pinfunction "C_C") (pintype "passive"))
      (node (ref "R21") (pin "2") (pinfunction "2_2") (pintype "passive"))
    )
    (net (code "39") (name "Net-(LED6-PadC)") (class "Default")
      (node (ref "LED6") (pin "C") (pinfunction "C_C") (pintype "passive"))
      (node (ref "R25") (pin "2") (pinfunction "2_2") (pintype "passive"))
    )
    (net (code "40") (name "Net-(R14-Pad2)") (class "Default")
      (node (ref "R14") (pin "2") (pinfunction "2_2") (pintype "passive"))
      (node (ref "U6") (pin "GPIO15") (pinfunction "GPIO15_GPIO15") (pintype "bidirectional"))
    )
    (net (code "41") (name "Net-(R30-Pad1)") (class "Default")
      (node (ref "R30") (pin "1") (pinfunction "1_1") (pintype "passive"))
      (node (ref "U6") (pin "CH_PD") (pinfunction "CH_PD_CH_PD") (pintype "bidirectional"))
    )
    (net (code "42") (name "Net-(S1-O)") (class "Default")
      (node (ref "S1") (pin "1") (pinfunction "O_1") (pintype "passive"))
      (node (ref "SV2") (pin "1") (pinfunction "S_1") (pintype "passive"))
    )
    (net (code "43") (name "Net-(SV1A-S)") (class "Default")
      (node (ref "SV1") (pin "1") (pinfunction "S_1") (pintype "passive"))
      (node (ref "SV2") (pin "2") (pinfunction "S_2") (pintype "passive"))
    )
    (net (code "44") (name "Net-(U$1-CHANNELIN{slash}OUT0)") (class "Default")
      (node (ref "U$1") (pin "9") (pinfunction "CHANNELIN/OUT0_9") (pintype "bidirectional"))
      (node (ref "U1") (pin "1") (pinfunction "1B_1") (pintype "passive"))
    )
    (net (code "45") (name "Net-(U$1-CHANNELIN{slash}OUT1)") (class "Default")
      (node (ref "U$1") (pin "8") (pinfunction "CHANNELIN/OUT1_8") (pintype "bidirectional"))
      (node (ref "U1") (pin "2") (pinfunction "2B_2") (pintype "passive"))
    )
    (net (code "46") (name "Net-(U$1-CHANNELIN{slash}OUT2)") (class "Default")
      (node (ref "U$1") (pin "7") (pinfunction "CHANNELIN/OUT2_7") (pintype "bidirectional"))
      (node (ref "U1") (pin "3") (pinfunction "3B_3") (pintype "passive"))
    )
    (net (code "47") (name "Net-(U$1-CHANNELIN{slash}OUT3)") (class "Default")
      (node (ref "U$1") (pin "6") (pinfunction "CHANNELIN/OUT3_6") (pintype "bidirectional"))
      (node (ref "U1") (pin "4") (pinfunction "4B_4") (pintype "passive"))
    )
    (net (code "48") (name "Net-(U$1-CHANNELIN{slash}OUT4)") (class "Default")
      (node (ref "U$1") (pin "5") (pinfunction "CHANNELIN/OUT4_5") (pintype "bidirectional"))
      (node (ref "U1") (pin "5") (pinfunction "5B_5") (pintype "passive"))
    )
    (net (code "49") (name "Net-(U$1-CHANNELIN{slash}OUT5)") (class "Default")
      (node (ref "U$1") (pin "4") (pinfunction "CHANNELIN/OUT5_4") (pintype "bidirectional"))
      (node (ref "U1") (pin "6") (pinfunction "6B_6") (pintype "passive"))
    )
    (net (code "50") (name "Net-(U$1-CHANNELIN{slash}OUT6)") (class "Default")
      (node (ref "U$1") (pin "3") (pinfunction "CHANNELIN/OUT6_3") (pintype "bidirectional"))
      (node (ref "U1") (pin "7") (pinfunction "7B_7") (pintype "passive"))
    )
    (net (code "51") (name "Net-(U$1-CHANNELIN{slash}OUT7)") (class "Default")
      (node (ref "U$1") (pin "2") (pinfunction "CHANNELIN/OUT7_2") (pintype "bidirectional"))
      (node (ref "U1") (pin "8") (pinfunction "8B_8") (pintype "passive"))
    )
    (net (code "52") (name "Net-(U$1-CHANNELIN{slash}OUT8)") (class "Default")
      (node (ref "U$1") (pin "23") (pinfunction "CHANNELIN/OUT8_23") (pintype "bidirectional"))
      (node (ref "U2") (pin "1") (pinfunction "1B_1") (pintype "passive"))
    )
    (net (code "53") (name "Net-(U$1-CHANNELIN{slash}OUT9)") (class "Default")
      (node (ref "U$1") (pin "22") (pinfunction "CHANNELIN/OUT9_22") (pintype "bidirectional"))
      (node (ref "U2") (pin "2") (pinfunction "2B_2") (pintype "passive"))
    )
    (net (code "54") (name "Net-(U$1-CHANNELIN{slash}OUT10)") (class "Default")
      (node (ref "U$1") (pin "21") (pinfunction "CHANNELIN/OUT10_21") (pintype "bidirectional"))
      (node (ref "U2") (pin "3") (pinfunction "3B_3") (pintype "passive"))
    )
    (net (code "55") (name "Net-(U$1-CHANNELIN{slash}OUT11)") (class "Default")
      (node (ref "U$1") (pin "20") (pinfunction "CHANNELIN/OUT11_20") (pintype "bidirectional"))
      (node (ref "U2") (pin "4") (pinfunction "4B_4") (pintype "passive"))
    )
    (net (code "56") (name "Net-(U$1-CHANNELIN{slash}OUT12)") (class "Default")
      (node (ref "U$1") (pin "19") (pinfunction "CHANNELIN/OUT12_19") (pintype "bidirectional"))
      (node (ref "U2") (pin "5") (pinfunction "5B_5") (pintype "passive"))
    )
    (net (code "57") (name "Net-(U$1-CHANNELIN{slash}OUT13)") (class "Default")
      (node (ref "U$1") (pin "18") (pinfunction "CHANNELIN/OUT13_18") (pintype "bidirectional"))
      (node (ref "U2") (pin "6") (pinfunction "6B_6") (pintype "passive"))
    )
    (net (code "58") (name "Net-(U$1-CHANNELIN{slash}OUT14)") (class "Default")
      (node (ref "U$1") (pin "17") (pinfunction "CHANNELIN/OUT14_17") (pintype "bidirectional"))
      (node (ref "U2") (pin "7") (pinfunction "7B_7") (pintype "passive"))
    )
    (net (code "59") (name "Net-(U$1-CHANNELIN{slash}OUT15)") (class "Default")
      (node (ref "U$1") (pin "16") (pinfunction "CHANNELIN/OUT15_16") (pintype "bidirectional"))
      (node (ref "U2") (pin "8") (pinfunction "8B_8") (pintype "passive"))
    )
    (net (code "60") (name "Net-(U$3-BYP)") (class "Default")
      (node (ref "C2") (pin "1") (pinfunction "1_1") (pintype "passive"))
      (node (ref "U$3") (pin "4") (pinfunction "BYP_4") (pintype "passive"))
    )
    (net (code "61") (name "Net-(U$3-~{SHDN})") (class "Default")
      (node (ref "R1") (pin "1") (pinfunction "1_1") (pintype "passive"))
      (node (ref "U$3") (pin "3") (pinfunction "~{SHDN}_3") (pintype "passive"))
    )
    (net (code "62") (name "Net-(U1-1C)") (class "Default")
      (node (ref "U1") (pin "18") (pinfunction "1C_18") (pintype "passive"))
      (node (ref "X1") (pin "8") (pinfunction "1_8") (pintype "passive"))
    )
    (net (code "63") (name "Net-(U1-2C)") (class "Default")
      (node (ref "U1") (pin "17") (pinfunction "2C_17") (pintype "passive"))
      (node (ref "X1") (pin "7") (pinfunction "1_7") (pintype "passive"))
    )
    (net (code "64") (name "Net-(U1-3C)") (class "Default")
      (node (ref "U1") (pin "16") (pinfunction "3C_16") (pintype "passive"))
      (node (ref "X1") (pin "4") (pinfunction "1_4") (pintype "passive"))
    )
    (net (code "65") (name "Net-(U1-4C)") (class "Default")
      (node (ref "U1") (pin "15") (pinfunction "4C_15") (pintype "passive"))
      (node (ref "X1") (pin "5") (pinfunction "1_5") (pintype "passive"))
    )
    (net (code "66") (name "Net-(U1-5C)") (class "Default")
      (node (ref "U1") (pin "14") (pinfunction "5C_14") (pintype "passive"))
      (node (ref "X1") (pin "6") (pinfunction "1_6") (pintype "passive"))
    )
    (net (code "67") (name "Net-(U1-6C)") (class "Default")
      (node (ref "U1") (pin "13") (pinfunction "6C_13") (pintype "passive"))
      (node (ref "X1") (pin "13") (pinfunction "1_13") (pintype "passive"))
    )
    (net (code "68") (name "Net-(U1-7C)") (class "Default")
      (node (ref "U1") (pin "12") (pinfunction "7C_12") (pintype "passive"))
      (node (ref "X1") (pin "14") (pinfunction "1_14") (pintype "passive"))
    )
    (net (code "69") (name "Net-(U1-8C)") (class "Default")
      (node (ref "U1") (pin "11") (pinfunction "8C_11") (pintype "passive"))
      (node (ref "X1") (pin "15") (pinfunction "1_15") (pintype "passive"))
    )
    (net (code "70") (name "Net-(U2-1C)") (class "Default")
      (node (ref "U2") (pin "18") (pinfunction "1C_18") (pintype "passive"))
      (node (ref "X1") (pin "12") (pinfunction "1_12") (pintype "passive"))
    )
    (net (code "71") (name "Net-(U2-2C)") (class "Default")
      (node (ref "U2") (pin "17") (pinfunction "2C_17") (pintype "passive"))
      (node (ref "X1") (pin "11") (pinfunction "1_11") (pintype "passive"))
    )
    (net (code "72") (name "Net-(U2-3C)") (class "Default")
      (node (ref "U2") (pin "16") (pinfunction "3C_16") (pintype "passive"))
      (node (ref "X1") (pin "10") (pinfunction "1_10") (pintype "passive"))
    )
    (net (code "73") (name "Net-(U2-4C)") (class "Default")
      (node (ref "U2") (pin "15") (pinfunction "4C_15") (pintype "passive"))
      (node (ref "X1") (pin "9") (pinfunction "1_9") (pintype "passive"))
    )
    (net (code "74") (name "Net-(U4-ADECAY)") (class "Default")
      (node (ref "R10") (pin "1") (pinfunction "1_1") (pintype "passive"))
      (node (ref "U4") (pin "24") (pinfunction "ADECAY_24") (pintype "input"))
    )
    (net (code "75") (name "Net-(U4-AISEN)") (class "Default")
      (node (ref "R16") (pin "1") (pinfunction "1_1") (pintype "passive"))
      (node (ref "U4") (pin "2") (pinfunction "AISEN_2") (pintype "bidirectional"))
    )
    (net (code "76") (name "Net-(U4-AOUT1)") (class "Default")
      (node (ref "J3") (pin "4") (pinfunction "4_4") (pintype "passive"))
      (node (ref "J4") (pin "4") (pinfunction "4_4") (pintype "passive"))
      (node (ref "U4") (pin "1") (pinfunction "AOUT1_1") (pintype "output"))
    )
    (net (code "77") (name "Net-(U4-AOUT2)") (class "Default")
      (node (ref "J3") (pin "3") (pinfunction "3_3") (pintype "passive"))
      (node (ref "J4") (pin "3") (pinfunction "3_3") (pintype "passive"))
      (node (ref "U4") (pin "3") (pinfunction "AOUT2_3") (pintype "output"))
    )
    (net (code "78") (name "Net-(U4-AVREF)") (class "Default")
      (node (ref "U4") (pin "19") (pinfunction "AVREF_19") (pintype "input"))
      (node (ref "U4") (pin "20") (pinfunction "BVREF_20") (pintype "input"))
      (node (ref "U4") (pin "21") (pinfunction "VREFO_21") (pintype "output"))
    )
    (net (code "79") (name "Net-(U4-BDECAY)") (class "Default")
      (node (ref "R17") (pin "1") (pinfunction "1_1") (pintype "passive"))
      (node (ref "U4") (pin "23") (pinfunction "BDECAY_23") (pintype "input"))
    )
    (net (code "80") (name "Net-(U4-BISEN)") (class "Default")
      (node (ref "R15") (pin "1") (pinfunction "1_1") (pintype "passive"))
      (node (ref "U4") (pin "5") (pinfunction "BISEN_5") (pintype "bidirectional"))
    )
    (net (code "81") (name "Net-(U4-BOUT1)") (class "Default")
      (node (ref "J3") (pin "1") (pinfunction "1_1") (pintype "passive"))
      (node (ref "J4") (pin "1") (pinfunction "1_1") (pintype "passive"))
      (node (ref "U4") (pin "6") (pinfunction "BOUT1_6") (pintype "output"))
    )
    (net (code "82") (name "Net-(U4-BOUT2)") (class "Default")
      (node (ref "J3") (pin "2") (pinfunction "2_2") (pintype "passive"))
      (node (ref "J4") (pin "2") (pinfunction "2_2") (pintype "passive"))
      (node (ref "U4") (pin "4") (pinfunction "BOUT2_4") (pintype "output"))
    )
    (net (code "83") (name "Net-(U4-M0{slash}APHASE)") (class "Default")
      (node (ref "J8") (pin "2") (pinfunction "2_2") (pintype "passive"))
      (node (ref "U4") (pin "10") (pinfunction "M0/APHASE_10") (pintype "input"))
    )
    (net (code "84") (name "Net-(U4-M1)") (class "Default")
      (node (ref "J8") (pin "1") (pinfunction "1_1") (pintype "passive"))
      (node (ref "U4") (pin "11") (pinfunction "M1_11") (pintype "input"))
    )
    (net (code "85") (name "Net-(U4-NFAULT)") (class "Default")
      (node (ref "R18") (pin "1") (pinfunction "1_1") (pintype "passive"))
      (node (ref "U4") (pin "13") (pinfunction "NFAULT_13") (pintype "output"))
    )
    (net (code "86") (name "Net-(U4-NSLEEP)") (class "Default")
      (node (ref "R19") (pin "1") (pinfunction "1_1") (pintype "passive"))
      (node (ref "U4") (pin "22") (pinfunction "NSLEEP_22") (pintype "input"))
    )
    (net (code "87") (name "Net-(U4-VCP)") (class "Default")
      (node (ref "C9") (pin "1") (pinfunction "1_1") (pintype "passive"))
      (node (ref "U4") (pin "14") (pinfunction "VCP_14") (pintype "output"))
    )
    (net (code "88") (name "Net-(U5-ADECAY)") (class "Default")
      (node (ref "R2") (pin "1") (pinfunction "1_1") (pintype "passive"))
      (node (ref "U5") (pin "24") (pinfunction "ADECAY_24") (pintype "input"))
    )
    (net (code "89") (name "Net-(U5-AISEN)") (class "Default")
      (node (ref "R4") (pin "1") (pinfunction "1_1") (pintype "passive"))
      (node (ref "U5") (pin "2") (pinfunction "AISEN_2") (pintype "bidirectional"))
    )
    (net (code "90") (name "Net-(U5-AOUT1)") (class "Default")
      (node (ref "J2") (pin "4") (pinfunction "4_4") (pintype "passive"))
      (node (ref "J5") (pin "4") (pinfunction "4_4") (pintype "passive"))
      (node (ref "U5") (pin "1") (pinfunction "AOUT1_1") (pintype "output"))
    )
    (net (code "91") (name "Net-(U5-AOUT2)") (class "Default")
      (node (ref "J2") (pin "3") (pinfunction "3_3") (pintype "passive"))
      (node (ref "J5") (pin "3") (pinfunction "3_3") (pintype "passive"))
      (node (ref "U5") (pin "3") (pinfunction "AOUT2_3") (pintype "output"))
    )
    (net (code "92") (name "Net-(U5-AVREF)") (class "Default")
      (node (ref "U5") (pin "19") (pinfunction "AVREF_19") (pintype "input"))
      (node (ref "U5") (pin "20") (pinfunction "BVREF_20") (pintype "input"))
      (node (ref "U5") (pin "21") (pinfunction "VREFO_21") (pintype "output"))
    )
    (net (code "93") (name "Net-(U5-BDECAY)") (class "Default")
      (node (ref "R5") (pin "1") (pinfunction "1_1") (pintype "passive"))
      (node (ref "U5") (pin "23") (pinfunction "BDECAY_23") (pintype "input"))
    )
    (net (code "94") (name "Net-(U5-BISEN)") (class "Default")
      (node (ref "R3") (pin "1") (pinfunction "1_1") (pintype "passive"))
      (node (ref "U5") (pin "5") (pinfunction "BISEN_5") (pintype "bidirectional"))
    )
    (net (code "95") (name "Net-(U5-BOUT1)") (class "Default")
      (node (ref "J2") (pin "2") (pinfunction "2_2") (pintype "passive"))
      (node (ref "J5") (pin "2") (pinfunction "2_2") (pintype "passive"))
      (node (ref "U5") (pin "6") (pinfunction "BOUT1_6") (pintype "output"))
    )
    (net (code "96") (name "Net-(U5-BOUT2)") (class "Default")
      (node (ref "J2") (pin "1") (pinfunction "1_1") (pintype "passive"))
      (node (ref "J5") (pin "1") (pinfunction "1_1") (pintype "passive"))
      (node (ref "U5") (pin "4") (pinfunction "BOUT2_4") (pintype "output"))
    )
    (net (code "97") (name "Net-(U5-M0{slash}APHASE)") (class "Default")
      (node (ref "J6") (pin "2") (pinfunction "2_2") (pintype "passive"))
      (node (ref "U5") (pin "10") (pinfunction "M0/APHASE_10") (pintype "input"))
    )
    (net (code "98") (name "Net-(U5-M1)") (class "Default")
      (node (ref "J6") (pin "1") (pinfunction "1_1") (pintype "passive"))
      (node (ref "U5") (pin "11") (pinfunction "M1_11") (pintype "input"))
    )
    (net (code "99") (name "Net-(U5-NFAULT)") (class "Default")
      (node (ref "R8") (pin "1") (pinfunction "1_1") (pintype "passive"))
      (node (ref "U5") (pin "13") (pinfunction "NFAULT_13") (pintype "output"))
    )
    (net (code "100") (name "Net-(U5-NSLEEP)") (class "Default")
      (node (ref "R9") (pin "1") (pinfunction "1_1") (pintype "passive"))
      (node (ref "U5") (pin "22") (pinfunction "NSLEEP_22") (pintype "input"))
    )
    (net (code "101") (name "Net-(U5-VCP)") (class "Default")
      (node (ref "C11") (pin "1") (pinfunction "1_1") (pintype "passive"))
      (node (ref "U5") (pin "14") (pinfunction "VCP_14") (pintype "output"))
    )
    (net (code "102") (name "Net-(U7-ADC6)") (class "Default")
      (node (ref "J13") (pin "1") (pinfunction "1_1") (pintype "passive"))
      (node (ref "U7") (pin "19") (pinfunction "ADC6_19") (pintype "bidirectional"))
    )
    (net (code "103") (name "Net-(U7-ADC7)") (class "Default")
      (node (ref "J13") (pin "2") (pinfunction "2_2") (pintype "passive"))
      (node (ref "U7") (pin "22") (pinfunction "ADC7_22") (pintype "bidirectional"))
    )
    (net (code "104") (name "Net-(U7-PD0(RXD))") (class "Default")
      (node (ref "J12") (pin "1") (pinfunction "1_1") (pintype "passive"))
      (node (ref "U7") (pin "30") (pinfunction "PD0(RXD)_30") (pintype "bidirectional"))
    )
    (net (code "105") (name "Net-(U7-PD1(TXD))") (class "Default")
      (node (ref "J12") (pin "2") (pinfunction "2_2") (pintype "passive"))
      (node (ref "U7") (pin "31") (pinfunction "PD1(TXD)_31") (pintype "bidirectional"))
    )
    (net (code "106") (name "Net-(U7-PD7(AIN1))") (class "Default")
      (node (ref "LED6") (pin "A") (pinfunction "A_A") (pintype "passive"))
      (node (ref "U7") (pin "11") (pinfunction "PD7(AIN1)_11") (pintype "bidirectional"))
    )
    (net (code "107") (name "VCC") (class "Default")
      (node (ref "C21") (pin "1") (pinfunction "1_1") (pintype "passive"))
      (node (ref "C22") (pin "1") (pinfunction "1_1") (pintype "passive"))
      (node (ref "C23") (pin "1") (pinfunction "1_1") (pintype "passive"))
      (node (ref "C24") (pin "1") (pinfunction "1_1") (pintype "passive"))
      (node (ref "C5") (pin "1") (pinfunction "1_1") (pintype "passive"))
      (node (ref "S1") (pin "2") (pinfunction "P_2") (pintype "passive"))
      (node (ref "U3") (pin "1") (pinfunction "INPUT_1") (pintype "input"))
    )
    (net (code "108") (name "unconnected-(J10-Pad2)") (class "Default")
      (node (ref "J10") (pin "2") (pinfunction "2_2") (pintype "passive"))
    )
    (net (code "109") (name "unconnected-(S1-S-Pad3)") (class "Default")
      (node (ref "S1") (pin "3") (pinfunction "S_3") (pintype "passive"))
    )
    (net (code "110") (name "unconnected-(U2-5C-Pad14)") (class "Default")
      (node (ref "U2") (pin "14") (pinfunction "5C_14") (pintype "passive"))
    )
    (net (code "111") (name "unconnected-(U2-6C-Pad13)") (class "Default")
      (node (ref "U2") (pin "13") (pinfunction "6C_13") (pintype "passive"))
    )
    (net (code "112") (name "unconnected-(U2-7C-Pad12)") (class "Default")
      (node (ref "U2") (pin "12") (pinfunction "7C_12") (pintype "passive"))
    )
    (net (code "113") (name "unconnected-(U2-8C-Pad11)") (class "Default")
      (node (ref "U2") (pin "11") (pinfunction "8C_11") (pintype "passive"))
    )
    (net (code "114") (name "unconnected-(U6-*GPIO9-PadGPIO9)") (class "Default")
      (node (ref "U6") (pin "GPIO9") (pinfunction "*GPIO9_GPIO9") (pintype "bidirectional"))
    )
    (net (code "115") (name "unconnected-(U6-*GPIO10-PadGPIO10)") (class "Default")
      (node (ref "U6") (pin "GPIO10") (pinfunction "*GPIO10_GPIO10") (pintype "bidirectional"))
    )
    (net (code "116") (name "unconnected-(U6-PadADC)") (class "Default")
      (node (ref "U6") (pin "ADC") (pinfunction "ADC_ADC") (pintype "bidirectional"))
    )
    (net (code "117") (name "unconnected-(U6-PadCS0)") (class "Default")
      (node (ref "U6") (pin "CS0") (pinfunction "CS0_CS0") (pintype "bidirectional"))
    )
    (net (code "118") (name "unconnected-(U6-PadGPIO5)") (class "Default")
      (node (ref "U6") (pin "GPIO5") (pinfunction "GPIO5_GPIO5") (pintype "bidirectional"))
    )
    (net (code "119") (name "unconnected-(U6-PadGPIO12)") (class "Default")
      (node (ref "U6") (pin "GPIO12") (pinfunction "GPIO12_GPIO12") (pintype "bidirectional"))
    )
    (net (code "120") (name "unconnected-(U6-PadGPIO13)") (class "Default")
      (node (ref "U6") (pin "GPIO13") (pinfunction "GPIO13_GPIO13") (pintype "bidirectional"))
    )
    (net (code "121") (name "unconnected-(U6-PadGPIO16)") (class "Default")
      (node (ref "U6") (pin "GPIO16") (pinfunction "GPIO16_GPIO16") (pintype "bidirectional"))
    )
    (net (code "122") (name "unconnected-(U6-PadMISO)") (class "Default")
      (node (ref "U6") (pin "MISO") (pinfunction "MISO_MISO") (pintype "bidirectional"))
    )
    (net (code "123") (name "unconnected-(U6-PadMOSI)") (class "Default")
      (node (ref "U6") (pin "MOSI") (pinfunction "MOSI_MOSI") (pintype "bidirectional"))
    )
    (net (code "124") (name "unconnected-(U6-PadSCLK)") (class "Default")
      (node (ref "U6") (pin "SCLK") (pinfunction "SCLK_SCLK") (pintype "bidirectional"))
    )
    (net (code "125") (name "unconnected-(U7-AREF-Pad20)") (class "Default")
      (node (ref "U7") (pin "20") (pinfunction "AREF_20") (pintype "bidirectional"))
    )
    (net (code "126") (name "unconnected-(U7-PB6(XTAL1{slash}TOSC1)-Pad7)") (class "Default")
      (node (ref "U7") (pin "7") (pinfunction "PB6(XTAL1/TOSC1)_7") (pintype "bidirectional"))
    )
    (net (code "127") (name "unconnected-(U7-PB7(XTAL2{slash}TOSC2)-Pad8)") (class "Default")
      (node (ref "U7") (pin "8") (pinfunction "PB7(XTAL2/TOSC2)_8") (pintype "bidirectional"))
    )
    (net (code "128") (name "unconnected-(X1-Pad1)") (class "Default")
      (node (ref "X1") (pin "1") (pinfunction "1_1") (pintype "passive"))
    )
    (net (code "129") (name "unconnected-(X1I-1-Pad2)") (class "Default")
      (node (ref "X1") (pin "2") (pinfunction "1_2") (pintype "passive"))
    )
  )
)
